# tx.net
KiCad netlist of a schematic drawn in Altium Designer
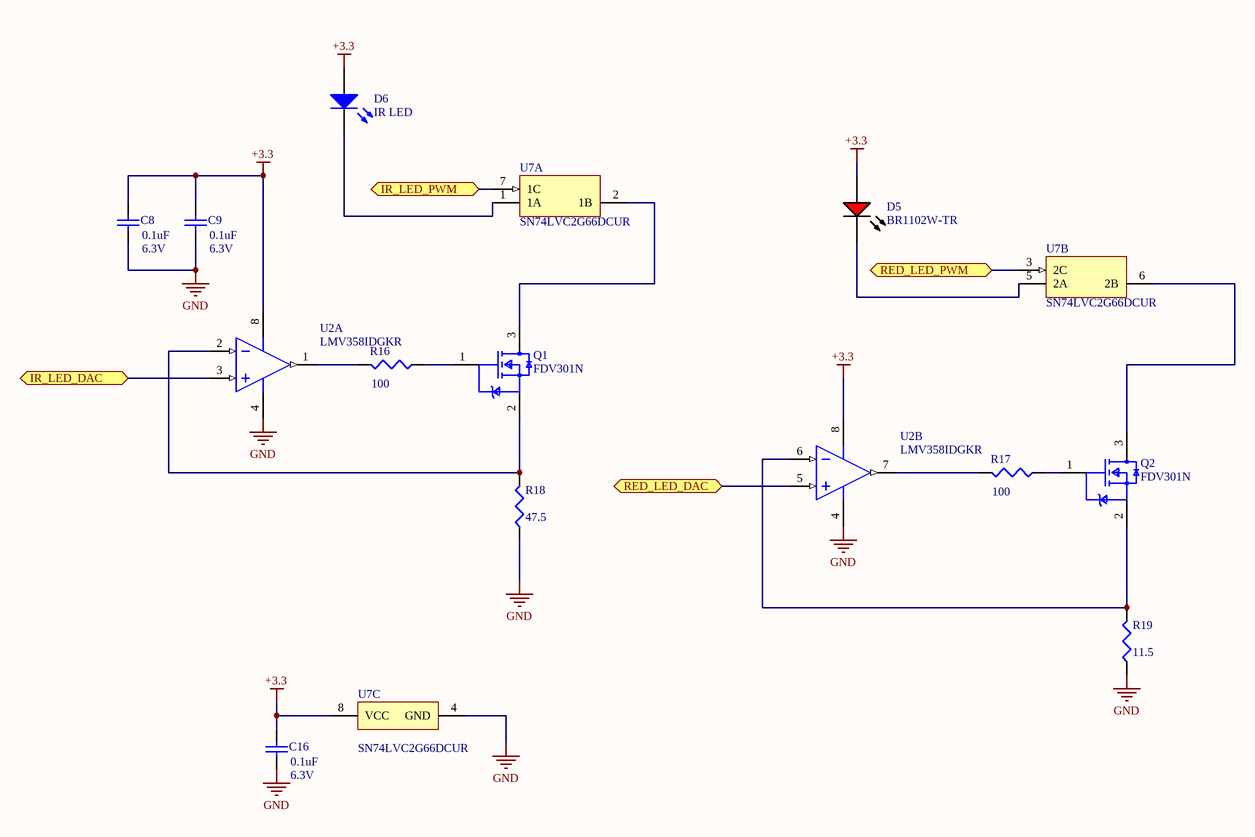
[diagram p0: tx.SchDoc]

(export (version "E")
  (design (tool "Eeschema 10.0.6"))
  (components
    (comp (ref "C8")
      (value "0.1uF")
      (footprint "1608[0603]")
      (description "Capacitor (Semiconductor SIM Model)")
      (fields
        (field (name "VOLTAGE") "6.3V")
        (field (name "MPN") "06036C104KAT4A")
        (field (name "MANUFACTURER") "AVX Corporation")
        (field (name "PUBLISHER") "Altium Limited")
      )
      (libsource (lib "Miscellaneous Devices") (part "Cap Semi"))
    )
    (comp (ref "C9")
      (value "0.1uF")
      (footprint "1608[0603]")
      (description "Capacitor (Semiconductor SIM Model)")
      (fields
        (field (name "VOLTAGE") "6.3V")
        (field (name "MPN") "06036C104KAT4A")
        (field (name "MANUFACTURER") "AVX Corporation")
        (field (name "PUBLISHER") "Altium Limited")
      )
      (libsource (lib "Miscellaneous Devices") (part "Cap Semi"))
    )
    (comp (ref "C16")
      (value "0.1uF")
      (footprint "1608[0603]")
      (description "Capacitor (Semiconductor SIM Model)")
      (fields
        (field (name "VOLTAGE") "6.3V")
        (field (name "MPN") "06036C104KAT4A")
        (field (name "MANUFACTURER") "AVX Corporation")
        (field (name "PUBLISHER") "Altium Limited")
      )
      (libsource (lib "Miscellaneous Devices") (part "Cap Semi"))
    )
    (comp (ref "D5")
      (value "BR1102W-TR")
      (footprint "STEC-1102W_V")
      (description "LED, Red, 647 nm, -30 to 85 degC, 2-Pin SMD, RoHS, Tape and Reel")
      (fields (field (name "MANUFACTURER") "Stanley Electric"))
      (libsource (lib "Altium Content Vault") (part "LED-RED-AK-2"))
    )
    (comp (ref "D6")
      (value "IR LED")
      (footprint "TIDA-014851:1206_180")
      (description "Typical INFRARED GaAs LED")
      (fields
        (field (name "MPN") "IR26-21C/L110/TR8")
        (field (name "MANUFACTURER") "Everlight Electronics Co Ltd")
        (field (name "PUBLISHER") "Altium Limited")
      )
      (libsource (lib "Miscellaneous Devices") (part "LED0"))
    )
    (comp (ref "Q1")
      (value "FDV301N")
      (footprint "FP-318-08-MFG")
      (description "MOSFET N-CH 25V 220MA SOT-23")
      (fields
        (field (name "MANUFACTURER") "ON Semiconductor")
        (field (name "OCTOPART") "https://octopart.com/fdv301n-on+semiconductor-84326713")
      )
      (libsource (lib "Altium Content Vault") (part "4b65c62267dd4506eaef0021093ec31"))
    )
    (comp (ref "Q2")
      (value "FDV301N")
      (footprint "FP-318-08-MFG")
      (description "MOSFET N-CH 25V 220MA SOT-23")
      (fields
        (field (name "MANUFACTURER") "ON Semiconductor")
        (field (name "OCTOPART") "https://octopart.com/fdv301n-on+semiconductor-84326713")
      )
      (libsource (lib "Altium Content Vault") (part "4b65c62267dd4506eaef0021093ec31"))
    )
    (comp (ref "R16")
      (value "100")
      (footprint "J1-0603")
      (description "Resistor")
      (fields
        (field (name "MPN") "ERJ-PA3F1000V")
        (field (name "MANUFACTURER") "Panasonic")
        (field (name "PUBLISHER") "Altium Limited")
      )
      (libsource (lib "Miscellaneous Devices") (part "Res3"))
    )
    (comp (ref "R17")
      (value "100")
      (footprint "J1-0603")
      (description "Resistor")
      (fields
        (field (name "MPN") "ERJ-PA3F1000V")
        (field (name "MANUFACTURER") "Panasonic")
        (field (name "PUBLISHER") "Altium Limited")
      )
      (libsource (lib "Miscellaneous Devices") (part "Res3"))
    )
    (comp (ref "R18")
      (value "47.5")
      (footprint "J1-0603")
      (description "Resistor")
      (fields
        (field (name "MPN") "RC0603FR-0747R5L")
        (field (name "MANUFACTURER") "Yageo")
        (field (name "PUBLISHER") "Altium Limited")
      )
      (libsource (lib "Miscellaneous Devices") (part "Res3"))
    )
    (comp (ref "R19")
      (value "11.5")
      (footprint "J1-0603")
      (description "Resistor")
      (fields
        (field (name "MPN") "ERJ-3EKF11R5V")
        (field (name "MANUFACTURER") "Panasonic")
        (field (name "PUBLISHER") "Altium Limited")
      )
      (libsource (lib "Miscellaneous Devices") (part "Res3"))
    )
    (comp (ref "U2")
      (value "LMV358IDGKR")
      (footprint "DGK0008A_M")
      (fields (field (name "MANUFACTURER") "Texas Instruments") (field (name "MPN") "LMV358SG-13"))
      (libsource (lib "Altium Content Vault") (part "TI-LMV358-8"))
    )
    (comp (ref "U7")
      (value "SN74LVC2G66DCUR")
      (footprint "DCU0008A_M")
      (description "Dual Analog Switch, DCU0008A, LARGE T&R")
      (fields
        (field (name "MANUFACTURER") "Texas Instruments")
        (field (name "GENERIC PART NUMBER") "SN74LVC2G66")
      )
      (libsource (lib "Altium Content Vault") (part "TI-SN74LVC2G66-8"))
    )
  )
  (nets
    (net (code "1") (name "+3.3") (class "Default")
      (node (ref "C16") (pin "2") (pinfunction "2_2") (pintype "passive"))
      (node (ref "C8") (pin "2") (pinfunction "2_2") (pintype "passive"))
      (node (ref "C9") (pin "2") (pinfunction "2_2") (pintype "passive"))
      (node (ref "D5") (pin "1") (pinfunction "A_1") (pintype "passive"))
      (node (ref "D6") (pin "1") (pinfunction "A_1") (pintype "passive"))
      (node (ref "U2") (pin "8") (pinfunction "VCC+_8") (pintype "power_in"))
      (node (ref "U7") (pin "8") (pinfunction "VCC_8") (pintype "power_in"))
    )
    (net (code "2") (name "/IR_LED_DAC") (class "Default")
      (node (ref "U2") (pin "3") (pinfunction "1IN+_3") (pintype "input"))
    )
    (net (code "3") (name "/IR_LED_PWM") (class "Default")
      (node (ref "U7") (pin "7") (pinfunction "1C_7") (pintype "input"))
    )
    (net (code "4") (name "/RED_LED_DAC") (class "Default")
      (node (ref "U2") (pin "5") (pinfunction "2IN+_5") (pintype "input"))
    )
    (net (code "5") (name "/RED_LED_PWM") (class "Default")
      (node (ref "U7") (pin "3") (pinfunction "2C_3") (pintype "input"))
    )
    (net (code "6") (name "GND") (class "Default")
      (node (ref "C16") (pin "1") (pinfunction "1_1") (pintype "passive"))
      (node (ref "C8") (pin "1") (pinfunction "1_1") (pintype "passive"))
      (node (ref "C9") (pin "1") (pinfunction "1_1") (pintype "passive"))
      (node (ref "R18") (pin "1") (pinfunction "1_1") (pintype "passive"))
      (node (ref "R19") (pin "1") (pinfunction "1_1") (pintype "passive"))
      (node (ref "U2") (pin "4") (pinfunction "GND_4") (pintype "power_in"))
      (node (ref "U7") (pin "4") (pinfunction "GND_4") (pintype "power_in"))
    )
    (net (code "7") (name "Net-(D5-K)") (class "Default")
      (node (ref "D5") (pin "2") (pinfunction "K_2") (pintype "passive"))
      (node (ref "U7") (pin "5") (pinfunction "2A_5") (pintype "passive"))
    )
    (net (code "8") (name "Net-(D6-K)") (class "Default")
      (node (ref "D6") (pin "2") (pinfunction "K_2") (pintype "passive"))
      (node (ref "U7") (pin "1") (pinfunction "1A_1") (pintype "passive"))
    )
    (net (code "9") (name "Net-(Q1-D)") (class "Default")
      (node (ref "Q1") (pin "3") (pinfunction "D_3") (pintype "passive"))
      (node (ref "U7") (pin "2") (pinfunction "1B_2") (pintype "passive"))
    )
    (net (code "10") (name "Net-(Q1-G)") (class "Default")
      (node (ref "Q1") (pin "1") (pinfunction "G_1") (pintype "passive"))
      (node (ref "R16") (pin "1") (pinfunction "1_1") (pintype "passive"))
    )
    (net (code "11") (name "Net-(Q1-S)") (class "Default")
      (node (ref "Q1") (pin "2") (pinfunction "S_2") (pintype "passive"))
      (node (ref "R18") (pin "2") (pinfunction "2_2") (pintype "passive"))
      (node (ref "U2") (pin "2") (pinfunction "1IN-_2") (pintype "input"))
    )
    (net (code "12") (name "Net-(Q2-D)") (class "Default")
      (node (ref "Q2") (pin "3") (pinfunction "D_3") (pintype "passive"))
      (node (ref "U7") (pin "6") (pinfunction "2B_6") (pintype "passive"))
    )
    (net (code "13") (name "Net-(Q2-G)") (class "Default")
      (node (ref "Q2") (pin "1") (pinfunction "G_1") (pintype "passive"))
      (node (ref "R17") (pin "1") (pinfunction "1_1") (pintype "passive"))
    )
    (net (code "14") (name "Net-(Q2-S)") (class "Default")
      (node (ref "Q2") (pin "2") (pinfunction "S_2") (pintype "passive"))
      (node (ref "R19") (pin "2") (pinfunction "2_2") (pintype "passive"))
      (node (ref "U2") (pin "6") (pinfunction "2IN-_6") (pintype "input"))
    )
    (net (code "15") (name "Net-(U2A-1OUT)") (class "Default")
      (node (ref "R16") (pin "2") (pinfunction "2_2") (pintype "passive"))
      (node (ref "U2") (pin "1") (pinfunction "1OUT_1") (pintype "output"))
    )
    (net (code "16") (name "Net-(U2B-2OUT)") (class "Default")
      (node (ref "R17") (pin "2") (pinfunction "2_2") (pintype "passive"))
      (node (ref "U2") (pin "7") (pinfunction "2OUT_7") (pintype "output"))
    )
  )
)
